# 03_UI_Outputs.net
KiCad netlist of a schematic drawn in Altium Designer
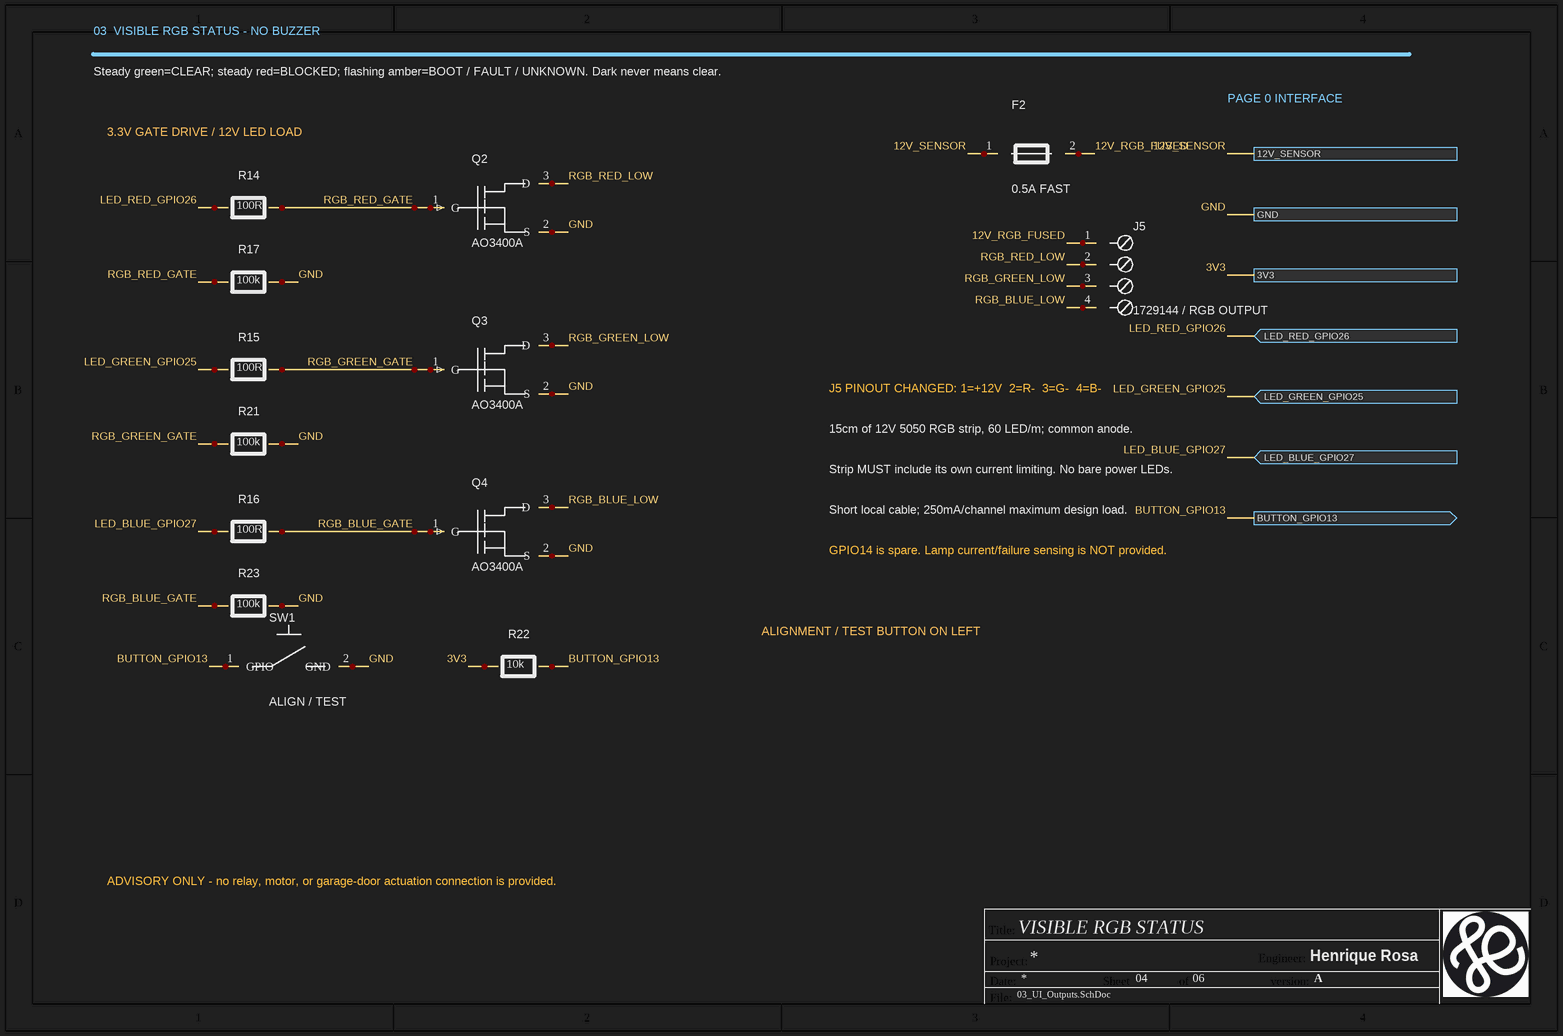
[diagram p0: 03_UI_Outputs.SchDoc]

(export (version "E")
  (design (tool "Eeschema 10.0.6"))
  (components
    (comp (ref "F2")
      (value "0.5A FAST")
      (description "RGB cable branch fuse; verify fault clearing with selected supply")
      (fields
        (field (name "MANUFACTURER") "Littelfuse")
        (field (name "MANUFACTURER PART NUMBER") "0451.500MRL")
      )
      (libsource (lib "*") (part "0451.500MRL"))
    )
    (comp (ref "J5")
      (value "1729144 / RGB OUTPUT")
      (footprint "PartSpecificFootprints:PHOENIX_1729144_MKDSN_4_508")
      (description "Common-anode analogue RGB strip; NOT addressable")
      (fields
        (field (name "MANUFACTURER") "Phoenix Contact")
        (field (name "MANUFACTURER PART NUMBER") "1729144")
      )
      (libsource (lib "PartSpecificComponents") (part "PHOENIX_1729144"))
    )
    (comp (ref "Q2")
      (value "AO3400A")
      (description "30V NMOS; Rds(on) specified at Vgs=2.5V; limit load to 250mA/channel")
      (fields (field (name "MANUFACTURER") "Alpha and Omega Semiconductor"))
      (libsource (lib "*") (part "AO3400A"))
    )
    (comp (ref "Q3")
      (value "AO3400A")
      (description "30V NMOS; Rds(on) specified at Vgs=2.5V; limit load to 250mA/channel")
      (fields (field (name "MANUFACTURER") "Alpha and Omega Semiconductor"))
      (libsource (lib "*") (part "AO3400A"))
    )
    (comp (ref "Q4")
      (value "AO3400A")
      (description "30V NMOS; Rds(on) specified at Vgs=2.5V; limit load to 250mA/channel")
      (fields (field (name "MANUFACTURER") "Alpha and Omega Semiconductor"))
      (libsource (lib "*") (part "AO3400A"))
    )
    (comp (ref "R14")
      (value "100R")
      (footprint "PCB - RESISTOR - CHIP - YAGEO RES 0805_2012:YAGEO RES 0805_2012")
      (description "MOSFET gate series resistor")
      (fields
        (field (name "MANUFACTURER") "Yageo")
        (field (name "MANUFACTURER PART NUMBER") "RC0805FR-07100RL")
      )
      (libsource (lib "Miscellaneous Devices") (part "RC0805FR-07100RL"))
    )
    (comp (ref "R15")
      (value "100R")
      (footprint "PCB - RESISTOR - CHIP - YAGEO RES 0805_2012:YAGEO RES 0805_2012")
      (description "MOSFET gate series resistor")
      (fields
        (field (name "MANUFACTURER") "Yageo")
        (field (name "MANUFACTURER PART NUMBER") "RC0805FR-07100RL")
      )
      (libsource (lib "Miscellaneous Devices") (part "RC0805FR-07100RL"))
    )
    (comp (ref "R16")
      (value "100R")
      (footprint "PCB - RESISTOR - CHIP - YAGEO RES 0805_2012:YAGEO RES 0805_2012")
      (description "MOSFET gate series resistor")
      (fields
        (field (name "MANUFACTURER") "Yageo")
        (field (name "MANUFACTURER PART NUMBER") "RC0805FR-07100RL")
      )
      (libsource (lib "Miscellaneous Devices") (part "RC0805FR-07100RL"))
    )
    (comp (ref "R17")
      (value "100k")
      (footprint "PCB - RESISTOR - CHIP - YAGEO RES 0805_2012:YAGEO RES 0805_2012")
      (description "Gate-source pull-down; off while ESP32 resets")
      (fields
        (field (name "MANUFACTURER") "Yageo")
        (field (name "MANUFACTURER PART NUMBER") "RC0805FR-07100KL")
      )
      (libsource (lib "Miscellaneous Devices") (part "RC0805FR-07100KL"))
    )
    (comp (ref "R21")
      (value "100k")
      (footprint "PCB - RESISTOR - CHIP - YAGEO RES 0805_2012:YAGEO RES 0805_2012")
      (description "Gate-source pull-down; off while ESP32 resets")
      (fields
        (field (name "MANUFACTURER") "Yageo")
        (field (name "MANUFACTURER PART NUMBER") "RC0805FR-07100KL")
      )
      (libsource (lib "Miscellaneous Devices") (part "RC0805FR-07100KL"))
    )
    (comp (ref "R22")
      (value "10k")
      (footprint "PCB - RESISTOR - CHIP - YAGEO RES 0805_2012:YAGEO RES 0805_2012")
      (description "Test button external pull-up")
      (fields
        (field (name "MANUFACTURER") "Yageo")
        (field (name "MANUFACTURER PART NUMBER") "RC0805FR-0710KL")
      )
      (libsource (lib "Miscellaneous Devices") (part "RC0805FR-0710KL"))
    )
    (comp (ref "R23")
      (value "100k")
      (footprint "PCB - RESISTOR - CHIP - YAGEO RES 0805_2012:YAGEO RES 0805_2012")
      (description "Gate-source pull-down; off while ESP32 resets")
      (fields
        (field (name "MANUFACTURER") "Yageo")
        (field (name "MANUFACTURER PART NUMBER") "RC0805FR-07100KL")
      )
      (libsource (lib "Miscellaneous Devices") (part "RC0805FR-07100KL"))
    )
    (comp (ref "SW1")
      (value "ALIGN / TEST")
      (description "Momentary test switch")
      (fields (field (name "MANUFACTURER") "Omron") (field (name "MANUFACTURER PART NUMBER") "B3FS-1000P"))
      (libsource (lib "*") (part "B3FS-1000P"))
    )
  )
  (nets
    (net (code "1") (name "/3V3") (class "Default")
      (node (ref "R22") (pin "1") (pinfunction "1_1") (pintype "passive"))
    )
    (net (code "2") (name "/12V_RGB_FUSED") (class "Default")
      (node (ref "F2") (pin "2") (pintype "passive"))
      (node (ref "J5") (pin "1") (pinfunction "+12V_1") (pintype "power_in"))
    )
    (net (code "3") (name "/12V_SENSOR") (class "Default") (node (ref "F2") (pin "1") (pintype "passive")))
    (net (code "4") (name "/BUTTON_GPIO13") (class "Default")
      (node (ref "R22") (pin "2") (pinfunction "2_2") (pintype "passive"))
      (node (ref "SW1") (pin "1") (pinfunction "GPIO_1") (pintype "passive"))
    )
    (net (code "5") (name "/GND") (class "Default")
      (node (ref "Q2") (pin "2") (pinfunction "S_2") (pintype "passive"))
      (node (ref "Q3") (pin "2") (pinfunction "S_2") (pintype "passive"))
      (node (ref "Q4") (pin "2") (pinfunction "S_2") (pintype "passive"))
      (node (ref "R17") (pin "2") (pinfunction "2_2") (pintype "passive"))
      (node (ref "R21") (pin "2") (pinfunction "2_2") (pintype "passive"))
      (node (ref "R23") (pin "2") (pinfunction "2_2") (pintype "passive"))
      (node (ref "SW1") (pin "2") (pinfunction "GND_2") (pintype "passive"))
    )
    (net (code "6") (name "/LED_BLUE_GPIO27") (class "Default")
      (node (ref "R16") (pin "1") (pinfunction "1_1") (pintype "passive"))
    )
    (net (code "7") (name "/LED_GREEN_GPIO25") (class "Default")
      (node (ref "R15") (pin "1") (pinfunction "1_1") (pintype "passive"))
    )
    (net (code "8") (name "/LED_RED_GPIO26") (class "Default")
      (node (ref "R14") (pin "1") (pinfunction "1_1") (pintype "passive"))
    )
    (net (code "9") (name "/RGB_BLUE_GATE") (class "Default")
      (node (ref "Q4") (pin "1") (pinfunction "G_1") (pintype "input"))
      (node (ref "R16") (pin "2") (pinfunction "2_2") (pintype "passive"))
      (node (ref "R23") (pin "1") (pinfunction "1_1") (pintype "passive"))
    )
    (net (code "10") (name "/RGB_BLUE_LOW") (class "Default")
      (node (ref "J5") (pin "4") (pinfunction "B-_4") (pintype "passive"))
      (node (ref "Q4") (pin "3") (pinfunction "D_3") (pintype "passive"))
    )
    (net (code "11") (name "/RGB_GREEN_GATE") (class "Default")
      (node (ref "Q3") (pin "1") (pinfunction "G_1") (pintype "input"))
      (node (ref "R15") (pin "2") (pinfunction "2_2") (pintype "passive"))
      (node (ref "R21") (pin "1") (pinfunction "1_1") (pintype "passive"))
    )
    (net (code "12") (name "/RGB_GREEN_LOW") (class "Default")
      (node (ref "J5") (pin "3") (pinfunction "G-_3") (pintype "passive"))
      (node (ref "Q3") (pin "3") (pinfunction "D_3") (pintype "passive"))
    )
    (net (code "13") (name "/RGB_RED_GATE") (class "Default")
      (node (ref "Q2") (pin "1") (pinfunction "G_1") (pintype "input"))
      (node (ref "R14") (pin "2") (pinfunction "2_2") (pintype "passive"))
      (node (ref "R17") (pin "1") (pinfunction "1_1") (pintype "passive"))
    )
    (net (code "14") (name "/RGB_RED_LOW") (class "Default")
      (node (ref "J5") (pin "2") (pinfunction "R-_2") (pintype "passive"))
      (node (ref "Q2") (pin "3") (pinfunction "D_3") (pintype "passive"))
    )
  )
)
